# HBridge.net
KiCad netlist of a schematic drawn in Altium Designer
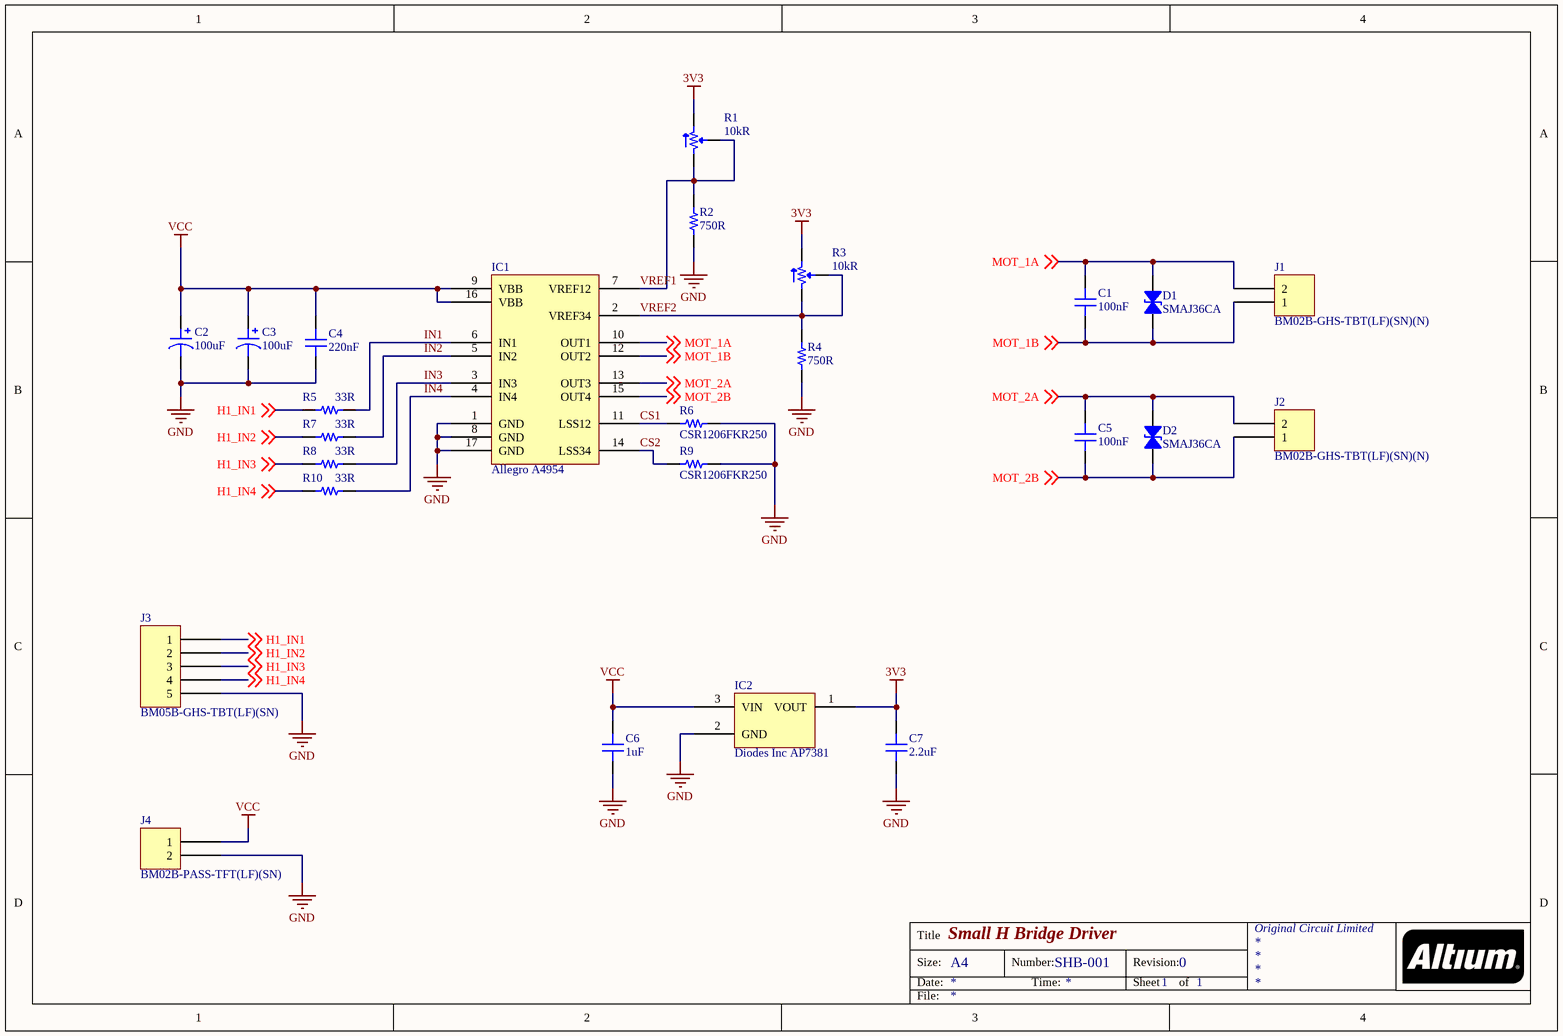
[diagram p0: HBridge.SchDoc]

(export (version "E")
  (design (tool "Eeschema 10.0.6"))
  (components
    (comp (ref "C1")
      (value "100nF")
      (footprint "CAP 0402/1005")
      (description "SMT Capacitor")
      (fields (field (name "TOLERANCE") "10%"))
      (libsource (lib "SCH - PASSIVES - CAPACITOR") (part "Capacitor"))
    )
    (comp (ref "C2")
      (value "100uF")
      (footprint "CAP ALUM 8.3MM")
      (description "SMT Polarised Capacitor")
      (fields (field (name "TOLERANCE") "20%") (field (name "VOLTAGE") "50V"))
      (libsource (lib "SCH - PASSIVES - POLARISED CAPACITOR") (part "Polarised Capacitor"))
    )
    (comp (ref "C3")
      (value "100uF")
      (footprint "CAP ALUM 8.3MM")
      (description "SMT Polarised Capacitor")
      (fields (field (name "TOLERANCE") "20%") (field (name "VOLTAGE") "50V"))
      (libsource (lib "SCH - PASSIVES - POLARISED CAPACITOR") (part "Polarised Capacitor"))
    )
    (comp (ref "C4")
      (value "220nF")
      (footprint "CAP 0402/1005")
      (description "SMT Capacitor")
      (fields (field (name "TOLERANCE") "10%"))
      (libsource (lib "SCH - PASSIVES - CAPACITOR") (part "Capacitor"))
    )
    (comp (ref "C5")
      (value "100nF")
      (footprint "CAP 0402/1005")
      (description "SMT Capacitor")
      (fields (field (name "TOLERANCE") "10%"))
      (libsource (lib "SCH - PASSIVES - CAPACITOR") (part "Capacitor"))
    )
    (comp (ref "C6")
      (value "1uF")
      (footprint "CAP 0603/1608")
      (description "SMT Capacitor")
      (fields (field (name "TOLERANCE") "10%"))
      (libsource (lib "SCH - PASSIVES - CAPACITOR") (part "Capacitor"))
    )
    (comp (ref "C7")
      (value "2.2uF")
      (footprint "CAP 0603/1608")
      (description "SMT Capacitor")
      (fields (field (name "TOLERANCE") "10%") (field (name "VOLTAGE") "10V"))
      (libsource (lib "SCH - PASSIVES - CAPACITOR") (part "Capacitor"))
    )
    (comp (ref "D1")
      (value "SMAJ36CA")
      (footprint "Bourns DO214AC SMA")
      (description "Bidirectional Zener Diode")
      (libsource (lib "SCH - DIODES - DIODE ZENER BIDIRECTIONAL") (part "Diode Zener Bidirectional"))
    )
    (comp (ref "D2")
      (value "SMAJ36CA")
      (footprint "Bourns DO214AC SMA")
      (description "Bidirectional Zener Diode")
      (libsource (lib "SCH - DIODES - DIODE ZENER BIDIRECTIONAL") (part "Diode Zener Bidirectional"))
    )
    (comp (ref "IC1")
      (value "Allegro A4954")
      (footprint "ALLEGRO TSSOP-16EP LP")
      (libsource (lib "SCH - DRIVER - MOTOR - ALLEGRO A4954") (part "Allegro A4954"))
    )
    (comp (ref "IC2")
      (value "Diodes Inc AP7381")
      (footprint "DIODES INC SOT-89")
      (description "150mA Low quiescent current fast transient low drop out linear regulator")
      (libsource (lib "SCH - POWER - LINEAR VREG - DIODES INC AP7381") (part "Diodes Inc AP7381"))
    )
    (comp (ref "J1")
      (value "BM02B-GHS-TBT(LF)(SN)(N)")
      (footprint "JST BM02B-GHS-TBT")
      (libsource (lib "SCH - CONNECTORS - 2 PIN") (part "2 Pin"))
    )
    (comp (ref "J2")
      (value "BM02B-GHS-TBT(LF)(SN)(N)")
      (footprint "JST BM02B-GHS-TBT")
      (libsource (lib "SCH - CONNECTORS - 2 PIN") (part "2 Pin"))
    )
    (comp (ref "J3")
      (value "BM05B-GHS-TBT(LF)(SN)")
      (footprint "JST BM05B-GHS-TBT")
      (libsource (lib "SCH - CONNECTORS - 5 PIN") (part "5 Pin"))
    )
    (comp (ref "J4")
      (value "BM02B-PASS-TFT(LF)(SN)")
      (footprint "JST BM02B-GHS-TBT")
      (libsource (lib "") (part "2 Pin_1"))
    )
    (comp (ref "R1")
      (value "10kR")
      (footprint "POT BOURNS TRIMPOT TC33X-1")
      (description "Potentiometer")
      (fields (field (name "TOLERANCE") "25%"))
      (libsource (lib "SCH - PASSIVES - POTENTIOMETER") (part "Potentiometer"))
    )
    (comp (ref "R2")
      (value "750R")
      (footprint "RES 0402/1005")
      (description "SMT Resistor")
      (fields (field (name "TOLERANCE") "1%"))
      (libsource (lib "SCH - PASSIVES - RESISTOR") (part "Resistor"))
    )
    (comp (ref "R3")
      (value "10kR")
      (footprint "POT BOURNS TRIMPOT TC33X-1")
      (description "Potentiometer")
      (fields (field (name "TOLERANCE") "25%"))
      (libsource (lib "SCH - PASSIVES - POTENTIOMETER") (part "Potentiometer"))
    )
    (comp (ref "R4")
      (value "750R")
      (footprint "RES 0402/1005")
      (description "SMT Resistor")
      (fields (field (name "TOLERANCE") "1%"))
      (libsource (lib "SCH - PASSIVES - RESISTOR") (part "Resistor"))
    )
    (comp (ref "R5")
      (value "33R")
      (footprint "RES 0402/1005")
      (description "SMT Resistor")
      (fields (field (name "TOLERANCE") "5%"))
      (libsource (lib "SCH - PASSIVES - RESISTOR") (part "Resistor"))
    )
    (comp (ref "R6")
      (value "CSR1206FKR250")
      (footprint "STACKPOLE CSR1210")
      (description "SMT Resistor")
      (fields (field (name "TOLERANCE") "1%"))
      (libsource (lib "SCH - PASSIVES - RESISTOR") (part "Resistor"))
    )
    (comp (ref "R7")
      (value "33R")
      (footprint "RES 0402/1005")
      (description "SMT Resistor")
      (fields (field (name "TOLERANCE") "5%"))
      (libsource (lib "SCH - PASSIVES - RESISTOR") (part "Resistor"))
    )
    (comp (ref "R8")
      (value "33R")
      (footprint "RES 0402/1005")
      (description "SMT Resistor")
      (fields (field (name "TOLERANCE") "5%"))
      (libsource (lib "SCH - PASSIVES - RESISTOR") (part "Resistor"))
    )
    (comp (ref "R9")
      (value "CSR1206FKR250")
      (footprint "STACKPOLE CSR1210")
      (description "SMT Resistor")
      (fields (field (name "TOLERANCE") "1%"))
      (libsource (lib "SCH - PASSIVES - RESISTOR") (part "Resistor"))
    )
    (comp (ref "R10")
      (value "33R")
      (footprint "RES 0402/1005")
      (description "SMT Resistor")
      (fields (field (name "TOLERANCE") "5%"))
      (libsource (lib "SCH - PASSIVES - RESISTOR") (part "Resistor"))
    )
  )
  (nets
    (net (code "1") (name "/CS1") (class "Default")
      (node (ref "IC1") (pin "11") (pinfunction "LSS12_11") (pintype "passive"))
      (node (ref "R6") (pin "1") (pinfunction "1_1") (pintype "passive"))
    )
    (net (code "2") (name "/CS2") (class "Default")
      (node (ref "IC1") (pin "14") (pinfunction "LSS34_14") (pintype "passive"))
      (node (ref "R9") (pin "1") (pinfunction "1_1") (pintype "passive"))
    )
    (net (code "3") (name "/IN1") (class "Default")
      (node (ref "IC1") (pin "6") (pinfunction "IN1_6") (pintype "passive"))
      (node (ref "R5") (pin "2") (pinfunction "2_2") (pintype "passive"))
    )
    (net (code "4") (name "/IN2") (class "Default")
      (node (ref "IC1") (pin "5") (pinfunction "IN2_5") (pintype "passive"))
      (node (ref "R7") (pin "2") (pinfunction "2_2") (pintype "passive"))
    )
    (net (code "5") (name "/IN3") (class "Default")
      (node (ref "IC1") (pin "3") (pinfunction "IN3_3") (pintype "passive"))
      (node (ref "R8") (pin "2") (pinfunction "2_2") (pintype "passive"))
    )
    (net (code "6") (name "/IN4") (class "Default")
      (node (ref "IC1") (pin "4") (pinfunction "IN4_4") (pintype "passive"))
      (node (ref "R10") (pin "2") (pinfunction "2_2") (pintype "passive"))
    )
    (net (code "7") (name "/VREF1") (class "Default")
      (node (ref "IC1") (pin "7") (pinfunction "VREF12_7") (pintype "passive"))
      (node (ref "R1") (pin "1") (pinfunction "1_1") (pintype "passive"))
      (node (ref "R1") (pin "2") (pinfunction "2_2") (pintype "passive"))
      (node (ref "R2") (pin "2") (pinfunction "2_2") (pintype "passive"))
    )
    (net (code "8") (name "/VREF2") (class "Default")
      (node (ref "IC1") (pin "2") (pinfunction "VREF34_2") (pintype "passive"))
      (node (ref "R3") (pin "1") (pinfunction "1_1") (pintype "passive"))
      (node (ref "R3") (pin "2") (pinfunction "2_2") (pintype "passive"))
      (node (ref "R4") (pin "2") (pinfunction "2_2") (pintype "passive"))
    )
    (net (code "9") (name "3V3") (class "Default")
      (node (ref "C7") (pin "2") (pinfunction "2_2") (pintype "passive"))
      (node (ref "IC2") (pin "1") (pinfunction "VOUT_1") (pintype "passive"))
      (node (ref "R1") (pin "3") (pinfunction "3_3") (pintype "passive"))
      (node (ref "R3") (pin "3") (pinfunction "3_3") (pintype "passive"))
    )
    (net (code "10") (name "GND") (class "Default")
      (node (ref "C2") (pin "2") (pinfunction "2_2") (pintype "passive"))
      (node (ref "C3") (pin "2") (pinfunction "2_2") (pintype "passive"))
      (node (ref "C4") (pin "2") (pinfunction "2_2") (pintype "passive"))
      (node (ref "C6") (pin "1") (pinfunction "1_1") (pintype "passive"))
      (node (ref "C7") (pin "1") (pinfunction "1_1") (pintype "passive"))
      (node (ref "IC1") (pin "1") (pinfunction "GND_1") (pintype "passive"))
      (node (ref "IC1") (pin "17") (pinfunction "GND_17") (pintype "passive"))
      (node (ref "IC1") (pin "8") (pinfunction "GND_8") (pintype "passive"))
      (node (ref "IC2") (pin "2") (pinfunction "GND_2") (pintype "passive"))
      (node (ref "J3") (pin "5") (pinfunction "5_5") (pintype "passive"))
      (node (ref "J4") (pin "2") (pinfunction "2_2") (pintype "passive"))
      (node (ref "R2") (pin "1") (pinfunction "1_1") (pintype "passive"))
      (node (ref "R4") (pin "1") (pinfunction "1_1") (pintype "passive"))
      (node (ref "R6") (pin "2") (pinfunction "2_2") (pintype "passive"))
      (node (ref "R9") (pin "2") (pinfunction "2_2") (pintype "passive"))
    )
    (net (code "11") (name "H1_IN1") (class "Default")
      (node (ref "J3") (pin "1") (pinfunction "1_1") (pintype "passive"))
      (node (ref "R5") (pin "1") (pinfunction "1_1") (pintype "passive"))
    )
    (net (code "12") (name "H1_IN2") (class "Default")
      (node (ref "J3") (pin "2") (pinfunction "2_2") (pintype "passive"))
      (node (ref "R7") (pin "1") (pinfunction "1_1") (pintype "passive"))
    )
    (net (code "13") (name "H1_IN3") (class "Default")
      (node (ref "J3") (pin "3") (pinfunction "3_3") (pintype "passive"))
      (node (ref "R8") (pin "1") (pinfunction "1_1") (pintype "passive"))
    )
    (net (code "14") (name "H1_IN4") (class "Default")
      (node (ref "J3") (pin "4") (pinfunction "4_4") (pintype "passive"))
      (node (ref "R10") (pin "1") (pinfunction "1_1") (pintype "passive"))
    )
    (net (code "15") (name "MOT_1A") (class "Default")
      (node (ref "C1") (pin "1") (pinfunction "1_1") (pintype "passive"))
      (node (ref "D1") (pin "2") (pinfunction "2_2") (pintype "passive"))
      (node (ref "IC1") (pin "10") (pinfunction "OUT1_10") (pintype "passive"))
      (node (ref "J1") (pin "2") (pinfunction "2_2") (pintype "passive"))
    )
    (net (code "16") (name "MOT_1B") (class "Default")
      (node (ref "C1") (pin "2") (pinfunction "2_2") (pintype "passive"))
      (node (ref "D1") (pin "1") (pinfunction "1_1") (pintype "passive"))
      (node (ref "IC1") (pin "12") (pinfunction "OUT2_12") (pintype "passive"))
      (node (ref "J1") (pin "1") (pinfunction "1_1") (pintype "passive"))
    )
    (net (code "17") (name "MOT_2A") (class "Default")
      (node (ref "C5") (pin "1") (pinfunction "1_1") (pintype "passive"))
      (node (ref "D2") (pin "2") (pinfunction "2_2") (pintype "passive"))
      (node (ref "IC1") (pin "13") (pinfunction "OUT3_13") (pintype "passive"))
      (node (ref "J2") (pin "2") (pinfunction "2_2") (pintype "passive"))
    )
    (net (code "18") (name "MOT_2B") (class "Default")
      (node (ref "C5") (pin "2") (pinfunction "2_2") (pintype "passive"))
      (node (ref "D2") (pin "1") (pinfunction "1_1") (pintype "passive"))
      (node (ref "IC1") (pin "15") (pinfunction "OUT4_15") (pintype "passive"))
      (node (ref "J2") (pin "1") (pinfunction "1_1") (pintype "passive"))
    )
    (net (code "19") (name "VCC") (class "Default")
      (node (ref "C2") (pin "1") (pinfunction "1_1") (pintype "passive"))
      (node (ref "C3") (pin "1") (pinfunction "1_1") (pintype "passive"))
      (node (ref "C4") (pin "1") (pinfunction "1_1") (pintype "passive"))
      (node (ref "C6") (pin "2") (pinfunction "2_2") (pintype "passive"))
      (node (ref "IC1") (pin "16") (pinfunction "VBB_16") (pintype "passive"))
      (node (ref "IC1") (pin "9") (pinfunction "VBB_9") (pintype "passive"))
      (node (ref "IC2") (pin "3") (pinfunction "VIN_3") (pintype "passive"))
      (node (ref "J4") (pin "1") (pinfunction "1_1") (pintype "passive"))
    )
  )
)
